# ISL6236A_Demo.net
KiCad netlist of a schematic drawn in Altium Designer
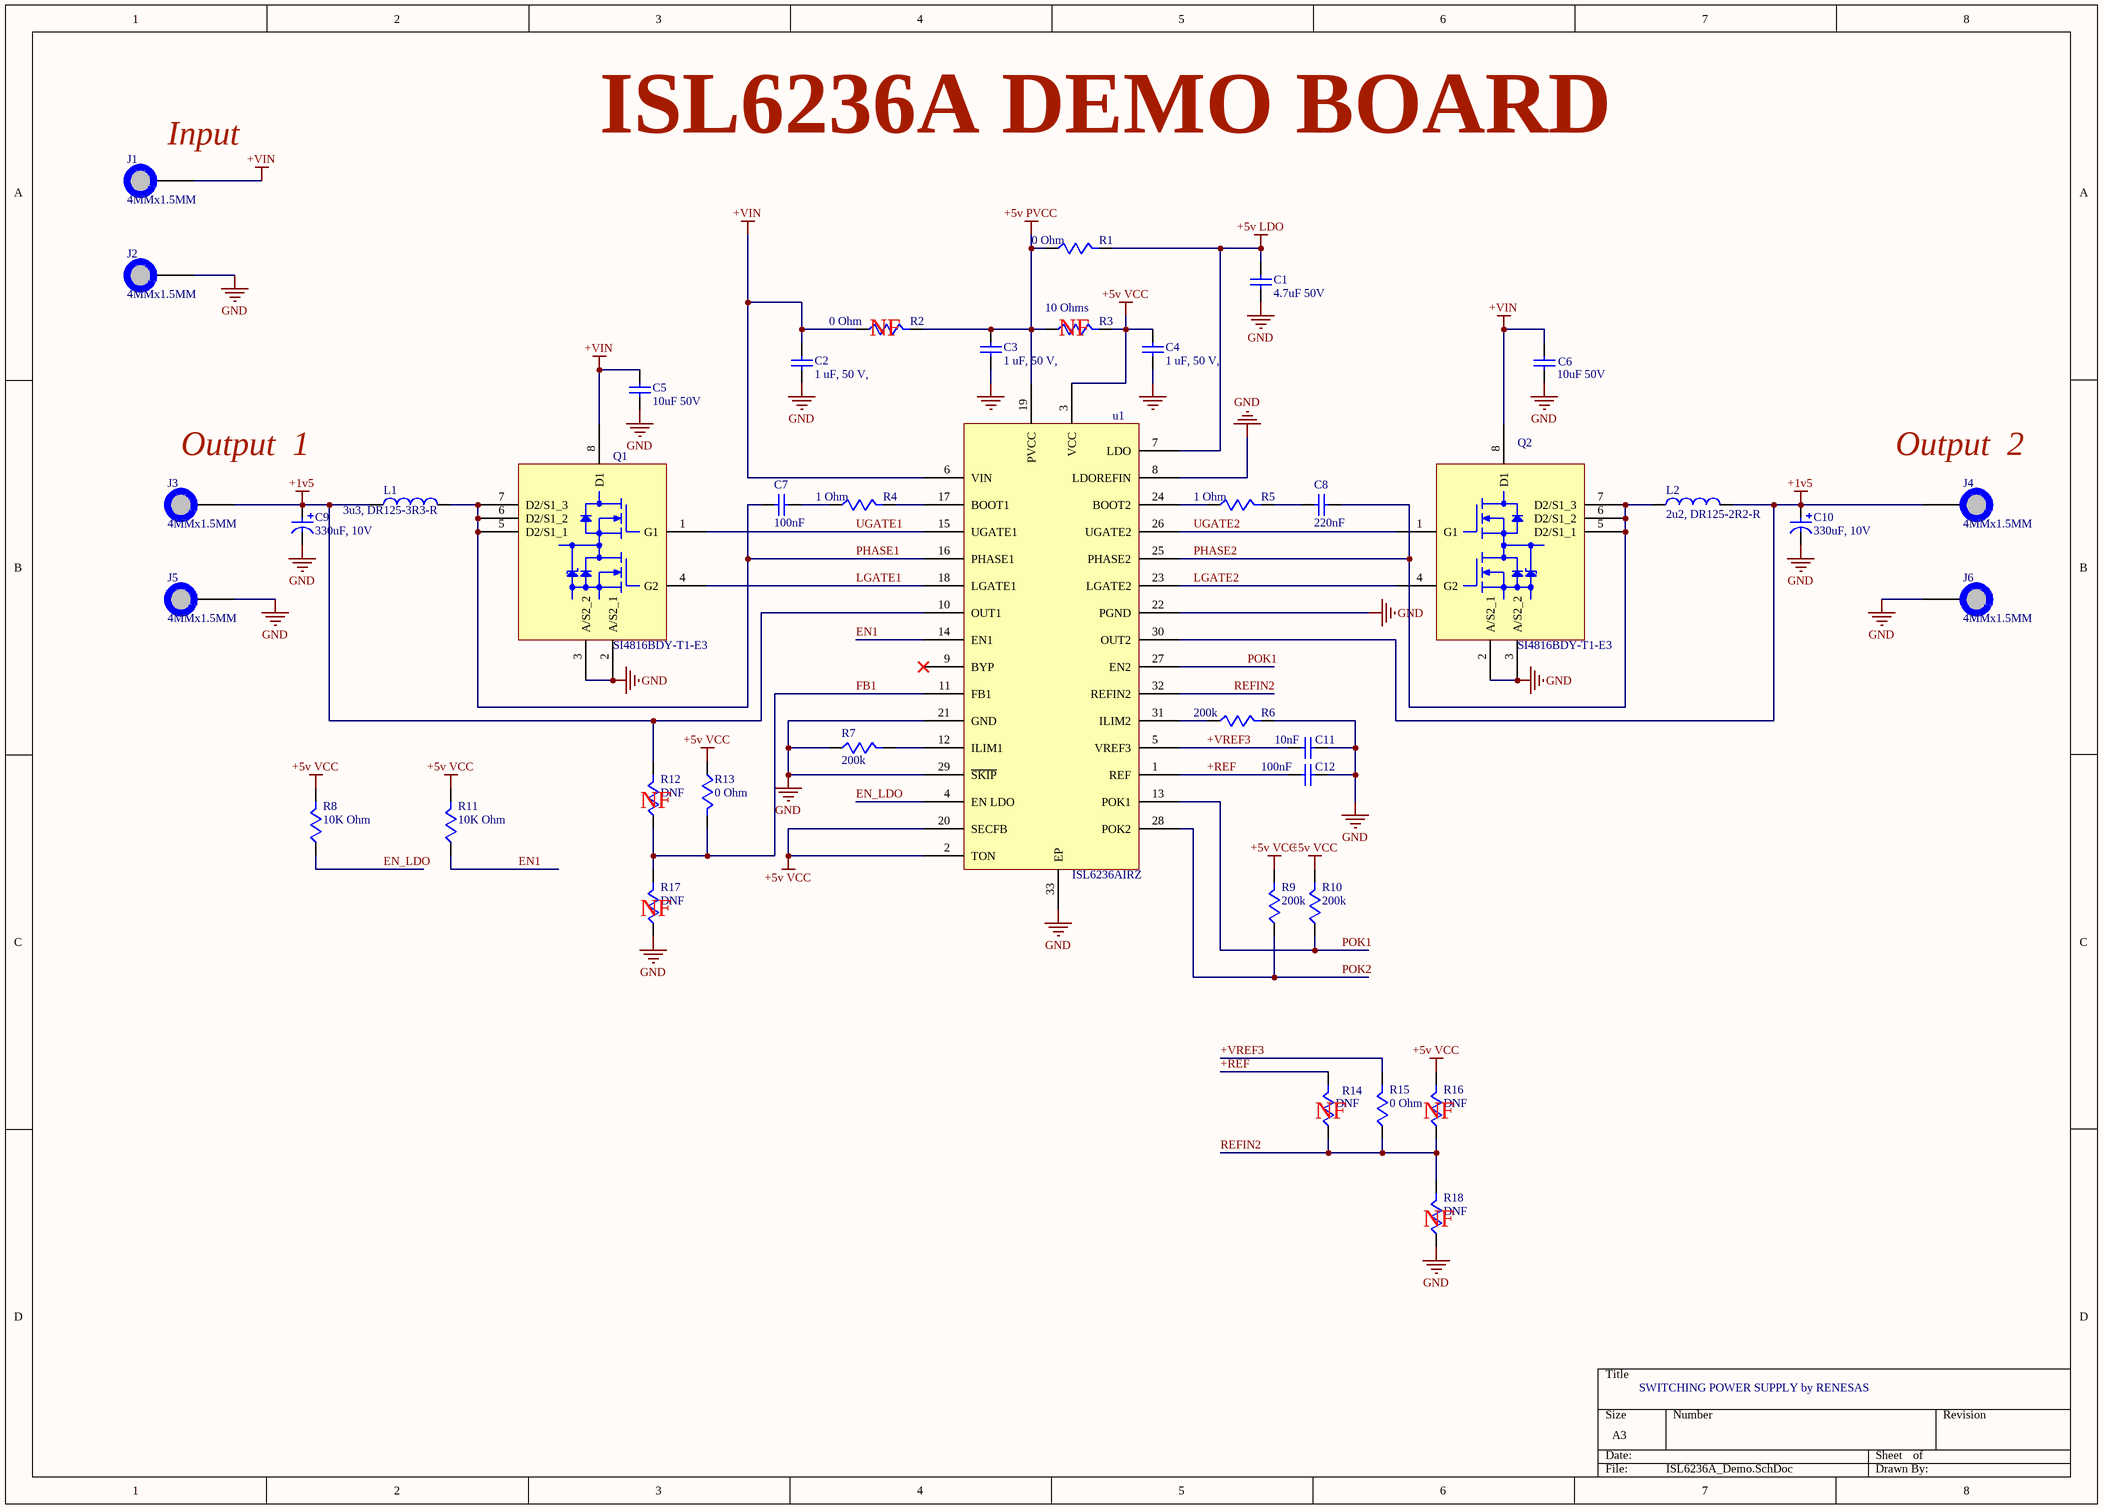
[diagram p0: ISL6236A_Demo.SchDoc]

(export (version "E")
  (design (tool "Eeschema 10.0.6"))
  (components
    (comp (ref "C1")
      (value "4.7uF 50V")
      (description "C Series 1206 4.7 uF 50 V ±10 % Tolerance X5R SMT Multilayer Ceramic Capacitor")
      (fields
        (field (name "MANUFACTURER") "TDK")
        (field (name "MANUFACTURER PART NUMBER") "C3216X5R1H475K160AB")
      )
      (libsource (lib "ISL6236A_Demo") (part "C3216X5R1H475K160AB"))
    )
    (comp (ref "C2")
      (value "1 uF, 50 V,")
      (description "Multilayer Ceramic Capacitor, 1 uF, 50 V, ± 10%, X7R, 0805 [2012 Metric]")
      (fields
        (field (name "MANUFACTURER") "TDK")
        (field (name "MANUFACTURER PART NUMBER") "C2012X7R1H105K125AB")
      )
      (libsource (lib "ISL6236A_Demo") (part "C2012X7R1H105K125AB"))
    )
    (comp (ref "C3")
      (value "1 uF, 50 V,")
      (description "Multilayer Ceramic Capacitor, 1 uF, 50 V, ± 10%, X7R, 0805 [2012 Metric]")
      (fields
        (field (name "MANUFACTURER") "TDK")
        (field (name "MANUFACTURER PART NUMBER") "C2012X7R1H105K125AB")
      )
      (libsource (lib "ISL6236A_Demo") (part "C2012X7R1H105K125AB"))
    )
    (comp (ref "C4")
      (value "1 uF, 50 V,")
      (description "Multilayer Ceramic Capacitor, 1 uF, 50 V, ± 10%, X7R, 0805 [2012 Metric]")
      (fields
        (field (name "MANUFACTURER") "TDK")
        (field (name "MANUFACTURER PART NUMBER") "C2012X7R1H105K125AB")
      )
      (libsource (lib "ISL6236A_Demo") (part "C2012X7R1H105K125AB"))
    )
    (comp (ref "C5")
      (value "10uF 50V")
      (description "Multilayer Ceramic Capacitor, 10 uF, 50 V, ± 10%, X5R, 1210 [3225 Metric]")
      (fields
        (field (name "MANUFACTURER") "Samsung")
        (field (name "MANUFACTURER PART NUMBER") "CL32A106KBJNNNE")
      )
      (libsource (lib "ISL6236A_Demo") (part "CL32A106KBJNNNE"))
    )
    (comp (ref "C6")
      (value "10uF 50V")
      (description "Multilayer Ceramic Capacitor, 10 uF, 50 V, ± 10%, X5R, 1210 [3225 Metric]")
      (fields
        (field (name "MANUFACTURER") "Samsung")
        (field (name "MANUFACTURER PART NUMBER") "CL32A106KBJNNNE")
      )
      (libsource (lib "ISL6236A_Demo") (part "CL32A106KBJNNNE"))
    )
    (comp (ref "C7")
      (value "100nF")
      (description "Multilayer Ceramic Capacitor, 0.1 uF, 50 V, ± 10%, X7R, 0805 [2012 Metric]")
      (fields
        (field (name "MANUFACTURER") "Yageo")
        (field (name "MANUFACTURER PART NUMBER") "CC0805KRX7R9BB104")
      )
      (libsource (lib "ISL6236A_Demo") (part "CC0805KRX7R9BB104"))
    )
    (comp (ref "C8")
      (value "220nF")
      (description "Multilayer Ceramic Capacitor, 0.22 uF, 50 V, ± 10%, X7R, 0805 [2012 Metric]")
      (fields
        (field (name "MANUFACTURER") "KEMET")
        (field (name "MANUFACTURER PART NUMBER") "C0805C224K5RACTU")
      )
      (libsource (lib "ISL6236A_Demo") (part "C0805C224K5RACTU"))
    )
    (comp (ref "C9")
      (value "330uF, 10V")
      (description "Cap Tant Solid 330uF 10V X CASE 20% (7.3 X 4.3 X 4mm) SMD 7343-43 0.004 Ohm 125 C T/R")
      (fields
        (field (name "MANUFACTURER") "KEMET")
        (field (name "MANUFACTURER PART NUMBER") "T530X337M010ATE004")
      )
      (libsource (lib "ISL6236A_Demo") (part "T530X337M010ATE004"))
    )
    (comp (ref "C10")
      (value "330uF, 10V")
      (description "Cap Tant Solid 330uF 10V X CASE 20% (7.3 X 4.3 X 4mm) SMD 7343-43 0.004 Ohm 125 C T/R")
      (fields
        (field (name "MANUFACTURER") "KEMET")
        (field (name "MANUFACTURER PART NUMBER") "T530X337M010ATE004")
      )
      (libsource (lib "ISL6236A_Demo") (part "T530X337M010ATE004"))
    )
    (comp (ref "C11")
      (value "10nF")
      (description "Multilayer Ceramic Capacitor, 0.01 uF, 50 V, ± 10%, X7R, 0805 [2012 Metric]")
      (fields
        (field (name "MANUFACTURER") "KEMET")
        (field (name "MANUFACTURER PART NUMBER") "C0805C103K5RACTU")
      )
      (libsource (lib "ISL6236A_Demo") (part "C0805C103K5RACTU"))
    )
    (comp (ref "C12")
      (value "100nF")
      (description "Multilayer Ceramic Capacitor, 0.1 uF, 50 V, ± 10%, X7R, 0805 [2012 Metric]")
      (fields
        (field (name "MANUFACTURER") "Yageo")
        (field (name "MANUFACTURER PART NUMBER") "CC0805KRX7R9BB104")
      )
      (libsource (lib "ISL6236A_Demo") (part "CC0805KRX7R9BB104"))
    )
    (comp (ref "J1")
      (value "4MMx1.5MM")
      (description "Pad with a hole 4mm x 1.5 mm")
      (libsource (lib "ISL6236A_Demo") (part "PAD_WITH_HOLE_4MMx1MM"))
    )
    (comp (ref "J2")
      (value "4MMx1.5MM")
      (description "Pad with a hole 4mm x 1.5 mm")
      (libsource (lib "ISL6236A_Demo") (part "PAD_WITH_HOLE_4MMx1MM"))
    )
    (comp (ref "J3")
      (value "4MMx1.5MM")
      (description "Pad with a hole 4mm x 1.5 mm")
      (libsource (lib "ISL6236A_Demo") (part "PAD_WITH_HOLE_4MMx1MM"))
    )
    (comp (ref "J4")
      (value "4MMx1.5MM")
      (description "Pad with a hole 4mm x 1.5 mm")
      (libsource (lib "ISL6236A_Demo") (part "PAD_WITH_HOLE_4MMx1MM"))
    )
    (comp (ref "J5")
      (value "4MMx1.5MM")
      (description "Pad with a hole 4mm x 1.5 mm")
      (libsource (lib "ISL6236A_Demo") (part "PAD_WITH_HOLE_4MMx1MM"))
    )
    (comp (ref "J6")
      (value "4MMx1.5MM")
      (description "Pad with a hole 4mm x 1.5 mm")
      (libsource (lib "ISL6236A_Demo") (part "PAD_WITH_HOLE_4MMx1MM"))
    )
    (comp (ref "L1")
      (value "3u3, DR125-3R3-R")
      (description "Inductor Power Shielded Drum Core 3.3uH 20% 100KHz Ferrite 9.26A 6.3mOhm DCR T/R")
      (fields
        (field (name "MANUFACTURER") "Eaton Cooper")
        (field (name "MANUFACTURER PART NUMBER") "DR125-3R3-R")
      )
      (libsource (lib "ISL6236A_Demo") (part "DR125-3R3-R"))
    )
    (comp (ref "L2")
      (value "2u2, DR125-2R2-R")
      (description "Ind Power Shielded Wirewound 2.2uH 20% 100KHz Ferrite 10.9A T/R")
      (fields
        (field (name "MANUFACTURER") "Eaton Cooper")
        (field (name "MANUFACTURER PART NUMBER") "DR125-2R2-R")
      )
      (libsource (lib "ISL6236A_Demo") (part "DR125-2R2-R"))
    )
    (comp (ref "Q1")
      (value "SI4816BDY-T1-E3")
      (description "Transistor MOSFET Array Dual N-CH 30V 5.8A/8.2A 8-Pin SOIC T/R")
      (fields (field (name "MANUFACTURER") "Vishay Siliconix"))
      (libsource (lib "ISL6236A_Demo") (part "SI4816BDY-T1-E3"))
    )
    (comp (ref "Q2")
      (value "SI4816BDY-T1-E3")
      (description "Transistor MOSFET Array Dual N-CH 30V 5.8A/8.2A 8-Pin SOIC T/R")
      (fields (field (name "MANUFACTURER") "Vishay Siliconix"))
      (libsource (lib "") (part "SI4816BDY-T1-E3_1"))
    )
    (comp (ref "R1")
      (value "0 Ohm")
      (description "Zero Ohm Resistor, 0805 [2012 Metric], Thick Film, 125 mW, 2 A, Surface Mount")
      (fields
        (field (name "MANUFACTURER") "Yageo")
        (field (name "MANUFACTURER PART NUMBER") "AC0805JR-070RL")
      )
      (libsource (lib "ISL6236A_Demo") (part "AC0805JR-070RL"))
    )
    (comp (ref "R2")
      (value "0 Ohm")
      (description "Zero Ohm Resistor, 0805 [2012 Metric], Thick Film, 125 mW, 2 A, Surface Mount")
      (fields
        (field (name "MANUFACTURER") "Yageo")
        (field (name "MANUFACTURER PART NUMBER") "AC0805JR-070RL")
      )
      (libsource (lib "ISL6236A_Demo") (part "AC0805JR-070RL"))
    )
    (comp (ref "R3")
      (value "10 Ohms")
      (description "SMD Chip Resistor, 10 Ohm, ± 1%, 125 mW, 0805 [2012 Metric], Thick Film, General Purpose")
      (fields
        (field (name "MANUFACTURER") "Yageo")
        (field (name "MANUFACTURER PART NUMBER") "AC0805FR-0710RL")
      )
      (libsource (lib "ISL6236A_Demo") (part "AC0805FR-0710RL"))
    )
    (comp (ref "R4")
      (value "1 Ohm")
      (description "SMD Chip Resistor, 1 Ohm, ± 1%, 125 mW, 0805 [2012 Metric], Thick Film, General Purpose")
      (fields
        (field (name "MANUFACTURER") "Yageo")
        (field (name "MANUFACTURER PART NUMBER") "AC0805FR-071RL")
      )
      (libsource (lib "ISL6236A_Demo") (part "AC0805FR-071RL"))
    )
    (comp (ref "R5")
      (value "1 Ohm")
      (description "SMD Chip Resistor, 1 Ohm, ± 1%, 125 mW, 0805 [2012 Metric], Thick Film, General Purpose")
      (fields
        (field (name "MANUFACTURER") "Yageo")
        (field (name "MANUFACTURER PART NUMBER") "AC0805FR-071RL")
      )
      (libsource (lib "ISL6236A_Demo") (part "AC0805FR-071RL"))
    )
    (comp (ref "R6")
      (value "200k")
      (description "SMD Chip Resistor, 200 kOhm, ± 1%, 125 mW, 0805 [2012 Metric], Thick Film, General Purpose")
      (fields
        (field (name "MANUFACTURER") "Yageo")
        (field (name "MANUFACTURER PART NUMBER") "AC0805FR-07200KL")
      )
      (libsource (lib "ISL6236A_Demo") (part "AC0805FR-07200KL"))
    )
    (comp (ref "R7")
      (value "200k")
      (description "SMD Chip Resistor, 200 kOhm, ± 1%, 125 mW, 0805 [2012 Metric], Thick Film, General Purpose")
      (fields
        (field (name "MANUFACTURER") "Yageo")
        (field (name "MANUFACTURER PART NUMBER") "AC0805FR-07200KL")
      )
      (libsource (lib "ISL6236A_Demo") (part "AC0805FR-07200KL"))
    )
    (comp (ref "R8")
      (value "10K Ohm")
      (description "SMD Chip Resistor, 10 kOhm, ± 1%, 125 mW, 0805 [2012 Metric], Thick Film, General Purpose")
      (fields
        (field (name "MANUFACTURER") "Yageo")
        (field (name "MANUFACTURER PART NUMBER") "RC0805FR-0710KL")
      )
      (libsource (lib "ISL6236A_Demo") (part "RC0805FR-0710KL"))
    )
    (comp (ref "R9")
      (value "200k")
      (description "SMD Chip Resistor, 200 kOhm, ± 1%, 125 mW, 0805 [2012 Metric], Thick Film, General Purpose")
      (fields
        (field (name "MANUFACTURER") "Yageo")
        (field (name "MANUFACTURER PART NUMBER") "AC0805FR-07200KL")
      )
      (libsource (lib "ISL6236A_Demo") (part "AC0805FR-07200KL"))
    )
    (comp (ref "R10")
      (value "200k")
      (description "SMD Chip Resistor, 200 kOhm, ± 1%, 125 mW, 0805 [2012 Metric], Thick Film, General Purpose")
      (fields
        (field (name "MANUFACTURER") "Yageo")
        (field (name "MANUFACTURER PART NUMBER") "AC0805FR-07200KL")
      )
      (libsource (lib "ISL6236A_Demo") (part "AC0805FR-07200KL"))
    )
    (comp (ref "R11")
      (value "10K Ohm")
      (description "SMD Chip Resistor, 10 kOhm, ± 1%, 125 mW, 0805 [2012 Metric], Thick Film, General Purpose")
      (fields
        (field (name "MANUFACTURER") "Yageo")
        (field (name "MANUFACTURER PART NUMBER") "RC0805FR-0710KL")
      )
      (libsource (lib "ISL6236A_Demo") (part "RC0805FR-0710KL"))
    )
    (comp (ref "R12") (value "DNF") (libsource (lib "ISL6236A_Demo") (part "RES")))
    (comp (ref "R13")
      (value "0 Ohm")
      (description "Zero Ohm Resistor, 0805 [2012 Metric], Thick Film, 125 mW, 2 A, Surface Mount")
      (fields
        (field (name "MANUFACTURER") "Yageo")
        (field (name "MANUFACTURER PART NUMBER") "AC0805JR-070RL")
      )
      (libsource (lib "ISL6236A_Demo") (part "AC0805JR-070RL"))
    )
    (comp (ref "R14") (value "DNF") (libsource (lib "ISL6236A_Demo") (part "RES")))
    (comp (ref "R15")
      (value "0 Ohm")
      (description "Zero Ohm Resistor, 0805 [2012 Metric], Thick Film, 125 mW, 2 A, Surface Mount")
      (fields
        (field (name "MANUFACTURER") "Yageo")
        (field (name "MANUFACTURER PART NUMBER") "AC0805JR-070RL")
      )
      (libsource (lib "ISL6236A_Demo") (part "AC0805JR-070RL"))
    )
    (comp (ref "R16") (value "DNF") (libsource (lib "ISL6236A_Demo") (part "RES")))
    (comp (ref "R17") (value "DNF") (libsource (lib "ISL6236A_Demo") (part "RES")))
    (comp (ref "R18") (value "DNF") (libsource (lib "ISL6236A_Demo") (part "RES")))
    (comp (ref "u1")
      (value "ISL6236AIRZ")
      (description "ISL6236A Series 25 V Dual Step-Down Switch-Mode Power-Supply Controller - QFN-32")
      (fields (field (name "MANUFACTURER") "Renesas"))
      (libsource (lib "ISL6236A_Demo") (part "ISL6236AIRZ"))
    )
  )
  (nets
    (net (code "1") (name "+1v5") (class "Default")
      (node (ref "C10") (pin "1") (pinfunction "1_1") (pintype "passive"))
      (node (ref "C9") (pin "1") (pinfunction "1_1") (pintype "passive"))
      (node (ref "J3") (pin "1") (pinfunction "1_1") (pintype "passive"))
      (node (ref "J4") (pin "1") (pinfunction "1_1") (pintype "passive"))
      (node (ref "L1") (pin "1") (pinfunction "1_1") (pintype "passive"))
      (node (ref "L2") (pin "2") (pinfunction "2_2") (pintype "passive"))
      (node (ref "R12") (pin "2") (pinfunction "2_2") (pintype "passive"))
      (node (ref "u1") (pin "10") (pinfunction "OUT1_10") (pintype "passive"))
      (node (ref "u1") (pin "30") (pinfunction "OUT2_30") (pintype "passive"))
    )
    (net (code "2") (name "+5v LDO") (class "Default")
      (node (ref "C1") (pin "2") (pinfunction "2_2") (pintype "passive"))
      (node (ref "R1") (pin "2") (pinfunction "2_2") (pintype "passive"))
      (node (ref "u1") (pin "7") (pinfunction "LDO_7") (pintype "passive"))
    )
    (net (code "3") (name "+5v PVCC") (class "Default")
      (node (ref "C3") (pin "2") (pinfunction "2_2") (pintype "passive"))
      (node (ref "R1") (pin "1") (pinfunction "1_1") (pintype "passive"))
      (node (ref "R2") (pin "2") (pinfunction "2_2") (pintype "passive"))
      (node (ref "R3") (pin "1") (pinfunction "1_1") (pintype "passive"))
      (node (ref "u1") (pin "19") (pinfunction "PVCC_19") (pintype "passive"))
    )
    (net (code "4") (name "+5v VCC") (class "Default")
      (node (ref "C4") (pin "2") (pinfunction "2_2") (pintype "passive"))
      (node (ref "R10") (pin "2") (pinfunction "2_2") (pintype "passive"))
      (node (ref "R11") (pin "2") (pinfunction "2_2") (pintype "passive"))
      (node (ref "R13") (pin "1") (pinfunction "1_1") (pintype "passive"))
      (node (ref "R16") (pin "2") (pinfunction "2_2") (pintype "passive"))
      (node (ref "R3") (pin "2") (pinfunction "2_2") (pintype "passive"))
      (node (ref "R8") (pin "2") (pinfunction "2_2") (pintype "passive"))
      (node (ref "R9") (pin "2") (pinfunction "2_2") (pintype "passive"))
      (node (ref "u1") (pin "2") (pinfunction "TON_2") (pintype "passive"))
      (node (ref "u1") (pin "20") (pinfunction "SECFB_20") (pintype "passive"))
      (node (ref "u1") (pin "3") (pinfunction "VCC_3") (pintype "passive"))
    )
    (net (code "5") (name "+VIN") (class "Default")
      (node (ref "C2") (pin "2") (pinfunction "2_2") (pintype "passive"))
      (node (ref "C5") (pin "2") (pinfunction "2_2") (pintype "passive"))
      (node (ref "C6") (pin "2") (pinfunction "2_2") (pintype "passive"))
      (node (ref "J1") (pin "1") (pinfunction "1_1") (pintype "passive"))
      (node (ref "Q1") (pin "8") (pinfunction "D1_8") (pintype "passive"))
      (node (ref "Q2") (pin "8") (pinfunction "D1_8") (pintype "passive"))
      (node (ref "R2") (pin "1") (pinfunction "1_1") (pintype "passive"))
      (node (ref "u1") (pin "6") (pinfunction "VIN_6") (pintype "passive"))
    )
    (net (code "6") (name "/+REF") (class "Default")
      (node (ref "C12") (pin "1") (pinfunction "1_1") (pintype "passive"))
      (node (ref "R14") (pin "2") (pinfunction "2_2") (pintype "passive"))
      (node (ref "u1") (pin "1") (pinfunction "REF_1") (pintype "passive"))
    )
    (net (code "7") (name "/+VREF3") (class "Default")
      (node (ref "C11") (pin "1") (pinfunction "1_1") (pintype "passive"))
      (node (ref "R15") (pin "2") (pinfunction "2_2") (pintype "passive"))
      (node (ref "u1") (pin "5") (pinfunction "VREF3_5") (pintype "passive"))
    )
    (net (code "8") (name "/EN1") (class "Default")
      (node (ref "R11") (pin "1") (pinfunction "1_1") (pintype "passive"))
      (node (ref "u1") (pin "14") (pinfunction "EN1_14") (pintype "passive"))
    )
    (net (code "9") (name "/EN_LDO") (class "Default")
      (node (ref "R8") (pin "1") (pinfunction "1_1") (pintype "passive"))
      (node (ref "u1") (pin "4") (pinfunction "EN_LDO_4") (pintype "passive"))
    )
    (net (code "10") (name "/FB1") (class "Default")
      (node (ref "R12") (pin "1") (pinfunction "1_1") (pintype "passive"))
      (node (ref "R13") (pin "2") (pinfunction "2_2") (pintype "passive"))
      (node (ref "R17") (pin "2") (pinfunction "2_2") (pintype "passive"))
      (node (ref "u1") (pin "11") (pinfunction "FB1_11") (pintype "passive"))
    )
    (net (code "11") (name "/LGATE1") (class "Default")
      (node (ref "Q1") (pin "4") (pinfunction "G2_4") (pintype "passive"))
      (node (ref "u1") (pin "18") (pinfunction "LGATE1_18") (pintype "passive"))
    )
    (net (code "12") (name "/LGATE2") (class "Default")
      (node (ref "Q2") (pin "4") (pinfunction "G2_4") (pintype "passive"))
      (node (ref "u1") (pin "23") (pinfunction "LGATE2_23") (pintype "passive"))
    )
    (net (code "13") (name "/PHASE1") (class "Default")
      (node (ref "C7") (pin "1") (pinfunction "1_1") (pintype "passive"))
      (node (ref "L1") (pin "2") (pinfunction "2_2") (pintype "passive"))
      (node (ref "Q1") (pin "5") (pinfunction "D2/S1_1_5") (pintype "passive"))
      (node (ref "Q1") (pin "6") (pinfunction "D2/S1_2_6") (pintype "passive"))
      (node (ref "Q1") (pin "7") (pinfunction "D2/S1_3_7") (pintype "passive"))
      (node (ref "u1") (pin "16") (pinfunction "PHASE1_16") (pintype "passive"))
    )
    (net (code "14") (name "/PHASE2") (class "Default")
      (node (ref "C8") (pin "2") (pinfunction "2_2") (pintype "passive"))
      (node (ref "L2") (pin "1") (pinfunction "1_1") (pintype "passive"))
      (node (ref "Q2") (pin "5") (pinfunction "D2/S1_1_5") (pintype "passive"))
      (node (ref "Q2") (pin "6") (pinfunction "D2/S1_2_6") (pintype "passive"))
      (node (ref "Q2") (pin "7") (pinfunction "D2/S1_3_7") (pintype "passive"))
      (node (ref "u1") (pin "25") (pinfunction "PHASE2_25") (pintype "passive"))
    )
    (net (code "15") (name "/POK1") (class "Default")
      (node (ref "R10") (pin "1") (pinfunction "1_1") (pintype "passive"))
      (node (ref "u1") (pin "13") (pinfunction "POK1_13") (pintype "passive"))
      (node (ref "u1") (pin "27") (pinfunction "EN2_27") (pintype "passive"))
    )
    (net (code "16") (name "/POK2") (class "Default")
      (node (ref "R9") (pin "1") (pinfunction "1_1") (pintype "passive"))
      (node (ref "u1") (pin "28") (pinfunction "POK2_28") (pintype "passive"))
    )
    (net (code "17") (name "/REFIN2") (class "Default")
      (node (ref "R14") (pin "1") (pinfunction "1_1") (pintype "passive"))
      (node (ref "R15") (pin "1") (pinfunction "1_1") (pintype "passive"))
      (node (ref "R16") (pin "1") (pinfunction "1_1") (pintype "passive"))
      (node (ref "R18") (pin "2") (pinfunction "2_2") (pintype "passive"))
      (node (ref "u1") (pin "32") (pinfunction "REFIN2_32") (pintype "passive"))
    )
    (net (code "18") (name "/UGATE1") (class "Default")
      (node (ref "Q1") (pin "1") (pinfunction "G1_1") (pintype "passive"))
      (node (ref "u1") (pin "15") (pinfunction "UGATE1_15") (pintype "passive"))
    )
    (net (code "19") (name "/UGATE2") (class "Default")
      (node (ref "Q2") (pin "1") (pinfunction "G1_1") (pintype "passive"))
      (node (ref "u1") (pin "26") (pinfunction "UGATE2_26") (pintype "passive"))
    )
    (net (code "20") (name "GND") (class "Default")
      (node (ref "C1") (pin "1") (pinfunction "1_1") (pintype "passive"))
      (node (ref "C10") (pin "2") (pinfunction "2_2") (pintype "passive"))
      (node (ref "C11") (pin "2") (pinfunction "2_2") (pintype "passive"))
      (node (ref "C12") (pin "2") (pinfunction "2_2") (pintype "passive"))
      (node (ref "C2") (pin "1") (pinfunction "1_1") (pintype "passive"))
      (node (ref "C3") (pin "1") (pinfunction "1_1") (pintype "passive"))
      (node (ref "C4") (pin "1") (pinfunction "1_1") (pintype "passive"))
      (node (ref "C5") (pin "1") (pinfunction "1_1") (pintype "passive"))
      (node (ref "C6") (pin "1") (pinfunction "1_1") (pintype "passive"))
      (node (ref "C9") (pin "2") (pinfunction "2_2") (pintype "passive"))
      (node (ref "J2") (pin "1") (pinfunction "1_1") (pintype "passive"))
      (node (ref "J5") (pin "1") (pinfunction "1_1") (pintype "passive"))
      (node (ref "J6") (pin "1") (pinfunction "1_1") (pintype "passive"))
      (node (ref "Q1") (pin "2") (pinfunction "A/S2_1_2") (pintype "passive"))
      (node (ref "Q1") (pin "3") (pinfunction "A/S2_2_3") (pintype "passive"))
      (node (ref "Q2") (pin "2") (pinfunction "A/S2_1_2") (pintype "passive"))
      (node (ref "Q2") (pin "3") (pinfunction "A/S2_2_3") (pintype "passive"))
      (node (ref "R17") (pin "1") (pinfunction "1_1") (pintype "passive"))
      (node (ref "R18") (pin "1") (pinfunction "1_1") (pintype "passive"))
      (node (ref "R6") (pin "2") (pinfunction "2_2") (pintype "passive"))
      (node (ref "R7") (pin "1") (pinfunction "1_1") (pintype "passive"))
      (node (ref "u1") (pin "21") (pinfunction "GND_21") (pintype "passive"))
      (node (ref "u1") (pin "22") (pinfunction "PGND_22") (pintype "passive"))
      (node (ref "u1") (pin "29") (pinfunction "~{SKIP}_29") (pintype "passive"))
      (node (ref "u1") (pin "33") (pinfunction "EP_33") (pintype "passive"))
      (node (ref "u1") (pin "8") (pinfunction "LDOREFIN_8") (pintype "passive"))
    )
    (net (code "21") (name "Net-(C7-Pad2)") (class "Default")
      (node (ref "C7") (pin "2") (pinfunction "2_2") (pintype "passive"))
      (node (ref "R4") (pin "1") (pinfunction "1_1") (pintype "passive"))
    )
    (net (code "22") (name "Net-(C8-Pad1)") (class "Default")
      (node (ref "C8") (pin "1") (pinfunction "1_1") (pintype "passive"))
      (node (ref "R5") (pin "2") (pinfunction "2_2") (pintype "passive"))
    )
    (net (code "23") (name "Net-(u1-BOOT1)") (class "Default")
      (node (ref "R4") (pin "2") (pinfunction "2_2") (pintype "passive"))
      (node (ref "u1") (pin "17") (pinfunction "BOOT1_17") (pintype "passive"))
    )
    (net (code "24") (name "Net-(u1-BOOT2)") (class "Default")
      (node (ref "R5") (pin "1") (pinfunction "1_1") (pintype "passive"))
      (node (ref "u1") (pin "24") (pinfunction "BOOT2_24") (pintype "passive"))
    )
    (net (code "25") (name "Net-(u1-ILIM1)") (class "Default")
      (node (ref "R7") (pin "2") (pinfunction "2_2") (pintype "passive"))
      (node (ref "u1") (pin "12") (pinfunction "ILIM1_12") (pintype "passive"))
    )
    (net (code "26") (name "Net-(u1-ILIM2)") (class "Default")
      (node (ref "R6") (pin "1") (pinfunction "1_1") (pintype "passive"))
      (node (ref "u1") (pin "31") (pinfunction "ILIM2_31") (pintype "passive"))
    )
    (net (code "27") (name "unconnected-(u1-BYP-Pad9)") (class "Default")
      (node (ref "u1") (pin "9") (pinfunction "BYP_9") (pintype "passive+no_connect"))
    )
  )
)
